# adg731-switches.net
KiCad netlist of a schematic drawn in Altium Designer
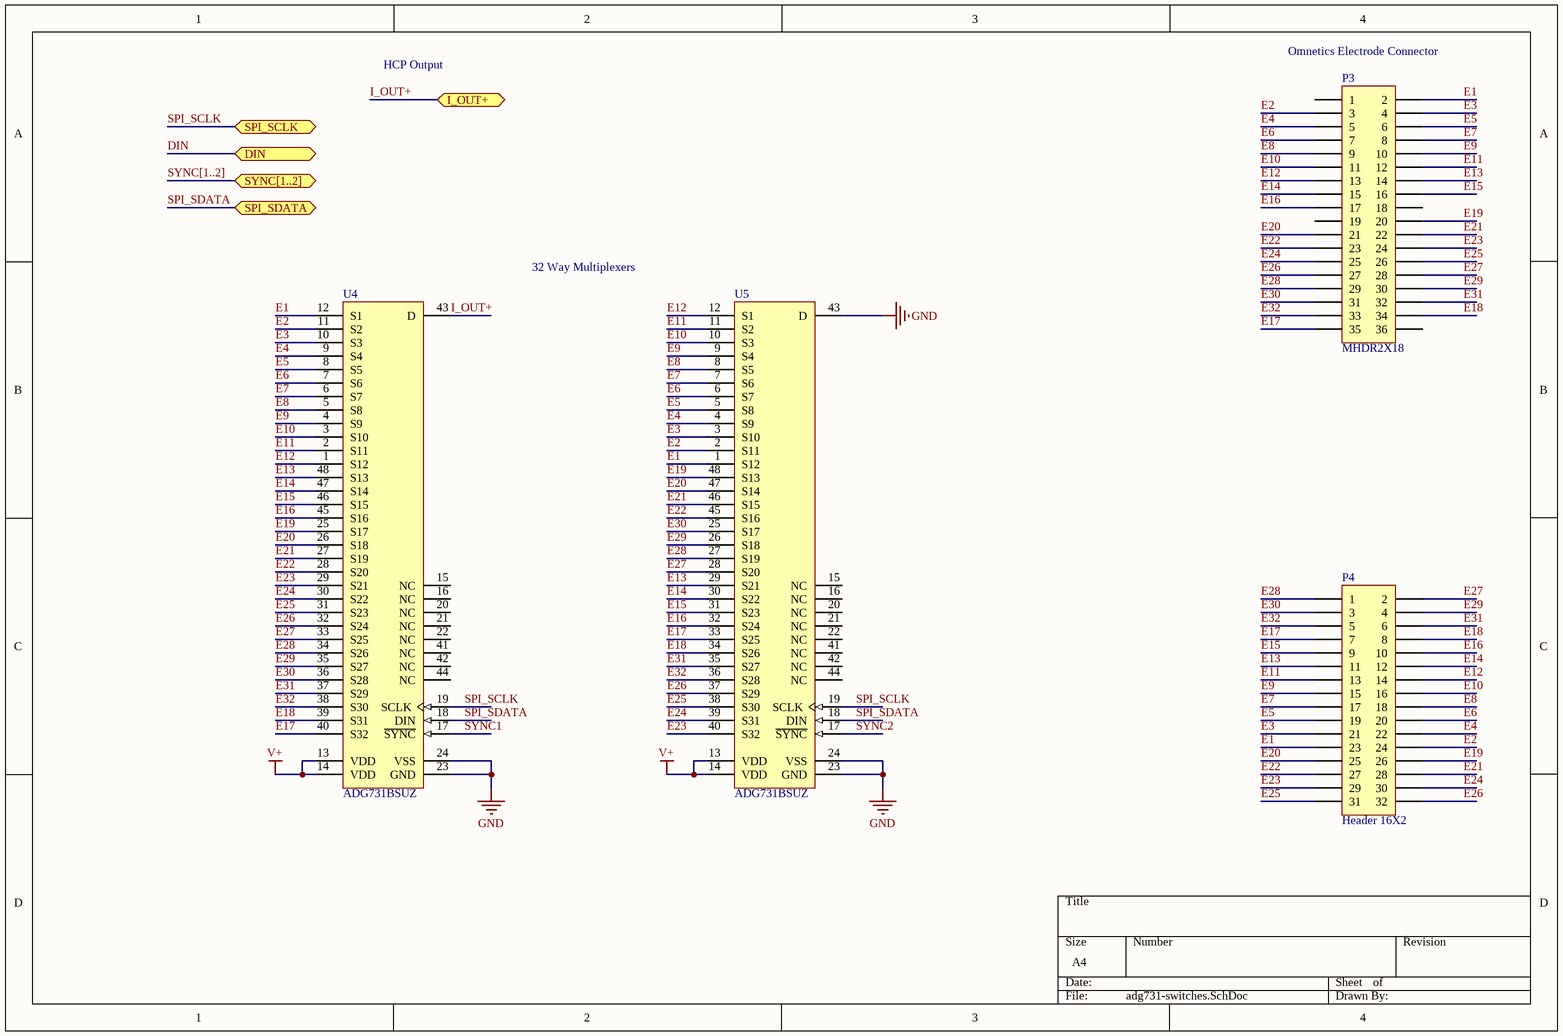
[diagram p0: adg731-switches.SchDoc]

(export (version "E")
  (design (tool "Eeschema 10.0.6"))
  (components
    (comp (ref "P3")
      (value "MHDR2X18")
      (footprint "A79025-001")
      (description "Header, 18-Pin, Dual row")
      (fields (field (name "PUBLISHER") "Altium Limited"))
      (libsource (lib "Miscellaneous Connectors") (part "MHDR2X18"))
    )
    (comp (ref "P4")
      (value "Header 16X2")
      (footprint "FTSH-117-XX-XXX-DH")
      (description "Header, 16-Pin, Dual row")
      (fields (field (name "PUBLISHER") "Altium Limited"))
      (libsource (lib "Miscellaneous Connectors") (part "Header 16X2"))
    )
    (comp (ref "U4")
      (value "ADG731BSUZ")
      (footprint "ADI-SU-48_N")
      (fields (field (name "MANUFACTURER") "Analog Devices"))
      (libsource (lib "Altium Content Vault") (part "CMP-0798-00240-1"))
    )
    (comp (ref "U5")
      (value "ADG731BSUZ")
      (footprint "ADI-SU-48_N")
      (fields (field (name "MANUFACTURER") "Analog Devices"))
      (libsource (lib "Altium Content Vault") (part "CMP-0798-00240-1"))
    )
  )
  (nets
    (net (code "2") (name "/E1") (class "Default")
      (node (ref "P3") (pin "2") (pinfunction "2_2") (pintype "passive"))
      (node (ref "P4") (pin "23") (pinfunction "23_23") (pintype "passive"))
      (node (ref "U4") (pin "12") (pinfunction "S1_12") (pintype "passive"))
      (node (ref "U5") (pin "1") (pinfunction "S12_1") (pintype "passive"))
    )
    (net (code "3") (name "/E2") (class "Default")
      (node (ref "P3") (pin "3") (pinfunction "3_3") (pintype "passive"))
      (node (ref "P4") (pin "24") (pinfunction "24_24") (pintype "passive"))
      (node (ref "U4") (pin "11") (pinfunction "S2_11") (pintype "passive"))
      (node (ref "U5") (pin "2") (pinfunction "S11_2") (pintype "passive"))
    )
    (net (code "4") (name "/E3") (class "Default")
      (node (ref "P3") (pin "4") (pinfunction "4_4") (pintype "passive"))
      (node (ref "P4") (pin "21") (pinfunction "21_21") (pintype "passive"))
      (node (ref "U4") (pin "10") (pinfunction "S3_10") (pintype "passive"))
      (node (ref "U5") (pin "3") (pinfunction "S10_3") (pintype "passive"))
    )
    (net (code "5") (name "/E4") (class "Default")
      (node (ref "P3") (pin "5") (pinfunction "5_5") (pintype "passive"))
      (node (ref "P4") (pin "22") (pinfunction "22_22") (pintype "passive"))
      (node (ref "U4") (pin "9") (pinfunction "S4_9") (pintype "passive"))
      (node (ref "U5") (pin "4") (pinfunction "S9_4") (pintype "passive"))
    )
    (net (code "6") (name "/E5") (class "Default")
      (node (ref "P3") (pin "6") (pinfunction "6_6") (pintype "passive"))
      (node (ref "P4") (pin "19") (pinfunction "19_19") (pintype "passive"))
      (node (ref "U4") (pin "8") (pinfunction "S5_8") (pintype "passive"))
      (node (ref "U5") (pin "5") (pinfunction "S8_5") (pintype "passive"))
    )
    (net (code "7") (name "/E6") (class "Default")
      (node (ref "P3") (pin "7") (pinfunction "7_7") (pintype "passive"))
      (node (ref "P4") (pin "20") (pinfunction "20_20") (pintype "passive"))
      (node (ref "U4") (pin "7") (pinfunction "S6_7") (pintype "passive"))
      (node (ref "U5") (pin "6") (pinfunction "S7_6") (pintype "passive"))
    )
    (net (code "8") (name "/E7") (class "Default")
      (node (ref "P3") (pin "8") (pinfunction "8_8") (pintype "passive"))
      (node (ref "P4") (pin "17") (pinfunction "17_17") (pintype "passive"))
      (node (ref "U4") (pin "6") (pinfunction "S7_6") (pintype "passive"))
      (node (ref "U5") (pin "7") (pinfunction "S6_7") (pintype "passive"))
    )
    (net (code "9") (name "/E8") (class "Default")
      (node (ref "P3") (pin "9") (pinfunction "9_9") (pintype "passive"))
      (node (ref "P4") (pin "18") (pinfunction "18_18") (pintype "passive"))
      (node (ref "U4") (pin "5") (pinfunction "S8_5") (pintype "passive"))
      (node (ref "U5") (pin "8") (pinfunction "S5_8") (pintype "passive"))
    )
    (net (code "10") (name "/E9") (class "Default")
      (node (ref "P3") (pin "10") (pinfunction "10_10") (pintype "passive"))
      (node (ref "P4") (pin "15") (pinfunction "15_15") (pintype "passive"))
      (node (ref "U4") (pin "4") (pinfunction "S9_4") (pintype "passive"))
      (node (ref "U5") (pin "9") (pinfunction "S4_9") (pintype "passive"))
    )
    (net (code "11") (name "/E10") (class "Default")
      (node (ref "P3") (pin "11") (pinfunction "11_11") (pintype "passive"))
      (node (ref "P4") (pin "16") (pinfunction "16_16") (pintype "passive"))
      (node (ref "U4") (pin "3") (pinfunction "S10_3") (pintype "passive"))
      (node (ref "U5") (pin "10") (pinfunction "S3_10") (pintype "passive"))
    )
    (net (code "12") (name "/E11") (class "Default")
      (node (ref "P3") (pin "12") (pinfunction "12_12") (pintype "passive"))
      (node (ref "P4") (pin "13") (pinfunction "13_13") (pintype "passive"))
      (node (ref "U4") (pin "2") (pinfunction "S11_2") (pintype "passive"))
      (node (ref "U5") (pin "11") (pinfunction "S2_11") (pintype "passive"))
    )
    (net (code "13") (name "/E12") (class "Default")
      (node (ref "P3") (pin "13") (pinfunction "13_13") (pintype "passive"))
      (node (ref "P4") (pin "14") (pinfunction "14_14") (pintype "passive"))
      (node (ref "U4") (pin "1") (pinfunction "S12_1") (pintype "passive"))
      (node (ref "U5") (pin "12") (pinfunction "S1_12") (pintype "passive"))
    )
    (net (code "14") (name "/E13") (class "Default")
      (node (ref "P3") (pin "14") (pinfunction "14_14") (pintype "passive"))
      (node (ref "P4") (pin "11") (pinfunction "11_11") (pintype "passive"))
      (node (ref "U4") (pin "48") (pinfunction "S13_48") (pintype "passive"))
      (node (ref "U5") (pin "29") (pinfunction "S21_29") (pintype "passive"))
    )
    (net (code "15") (name "/E14") (class "Default")
      (node (ref "P3") (pin "15") (pinfunction "15_15") (pintype "passive"))
      (node (ref "P4") (pin "12") (pinfunction "12_12") (pintype "passive"))
      (node (ref "U4") (pin "47") (pinfunction "S14_47") (pintype "passive"))
      (node (ref "U5") (pin "30") (pinfunction "S22_30") (pintype "passive"))
    )
    (net (code "16") (name "/E15") (class "Default")
      (node (ref "P3") (pin "16") (pinfunction "16_16") (pintype "passive"))
      (node (ref "P4") (pin "9") (pinfunction "9_9") (pintype "passive"))
      (node (ref "U4") (pin "46") (pinfunction "S15_46") (pintype "passive"))
      (node (ref "U5") (pin "31") (pinfunction "S23_31") (pintype "passive"))
    )
    (net (code "17") (name "/E16") (class "Default")
      (node (ref "P3") (pin "17") (pinfunction "17_17") (pintype "passive"))
      (node (ref "P4") (pin "10") (pinfunction "10_10") (pintype "passive"))
      (node (ref "U4") (pin "45") (pinfunction "S16_45") (pintype "passive"))
      (node (ref "U5") (pin "32") (pinfunction "S24_32") (pintype "passive"))
    )
    (net (code "18") (name "/E17") (class "Default")
      (node (ref "P3") (pin "35") (pinfunction "35_35") (pintype "passive"))
      (node (ref "P4") (pin "7") (pinfunction "7_7") (pintype "passive"))
      (node (ref "U4") (pin "40") (pinfunction "S32_40") (pintype "passive"))
      (node (ref "U5") (pin "33") (pinfunction "S25_33") (pintype "passive"))
    )
    (net (code "19") (name "/E18") (class "Default")
      (node (ref "P3") (pin "34") (pinfunction "34_34") (pintype "passive"))
      (node (ref "P4") (pin "8") (pinfunction "8_8") (pintype "passive"))
      (node (ref "U4") (pin "39") (pinfunction "S31_39") (pintype "passive"))
      (node (ref "U5") (pin "34") (pinfunction "S26_34") (pintype "passive"))
    )
    (net (code "20") (name "/E19") (class "Default")
      (node (ref "P3") (pin "20") (pinfunction "20_20") (pintype "passive"))
      (node (ref "P4") (pin "26") (pinfunction "26_26") (pintype "passive"))
      (node (ref "U4") (pin "25") (pinfunction "S17_25") (pintype "passive"))
      (node (ref "U5") (pin "48") (pinfunction "S13_48") (pintype "passive"))
    )
    (net (code "21") (name "/E20") (class "Default")
      (node (ref "P3") (pin "21") (pinfunction "21_21") (pintype "passive"))
      (node (ref "P4") (pin "25") (pinfunction "25_25") (pintype "passive"))
      (node (ref "U4") (pin "26") (pinfunction "S18_26") (pintype "passive"))
      (node (ref "U5") (pin "47") (pinfunction "S14_47") (pintype "passive"))
    )
    (net (code "22") (name "/E21") (class "Default")
      (node (ref "P3") (pin "22") (pinfunction "22_22") (pintype "passive"))
      (node (ref "P4") (pin "28") (pinfunction "28_28") (pintype "passive"))
      (node (ref "U4") (pin "27") (pinfunction "S19_27") (pintype "passive"))
      (node (ref "U5") (pin "46") (pinfunction "S15_46") (pintype "passive"))
    )
    (net (code "23") (name "/E22") (class "Default")
      (node (ref "P3") (pin "23") (pinfunction "23_23") (pintype "passive"))
      (node (ref "P4") (pin "27") (pinfunction "27_27") (pintype "passive"))
      (node (ref "U4") (pin "28") (pinfunction "S20_28") (pintype "passive"))
      (node (ref "U5") (pin "45") (pinfunction "S16_45") (pintype "passive"))
    )
    (net (code "24") (name "/E23") (class "Default")
      (node (ref "P3") (pin "24") (pinfunction "24_24") (pintype "passive"))
      (node (ref "P4") (pin "29") (pinfunction "29_29") (pintype "passive"))
      (node (ref "U4") (pin "29") (pinfunction "S21_29") (pintype "passive"))
      (node (ref "U5") (pin "40") (pinfunction "S32_40") (pintype "passive"))
    )
    (net (code "25") (name "/E24") (class "Default")
      (node (ref "P3") (pin "25") (pinfunction "25_25") (pintype "passive"))
      (node (ref "P4") (pin "30") (pinfunction "30_30") (pintype "passive"))
      (node (ref "U4") (pin "30") (pinfunction "S22_30") (pintype "passive"))
      (node (ref "U5") (pin "39") (pinfunction "S31_39") (pintype "passive"))
    )
    (net (code "26") (name "/E25") (class "Default")
      (node (ref "P3") (pin "26") (pinfunction "26_26") (pintype "passive"))
      (node (ref "P4") (pin "31") (pinfunction "31_31") (pintype "passive"))
      (node (ref "U4") (pin "31") (pinfunction "S23_31") (pintype "passive"))
      (node (ref "U5") (pin "38") (pinfunction "S30_38") (pintype "passive"))
    )
    (net (code "27") (name "/E26") (class "Default")
      (node (ref "P3") (pin "27") (pinfunction "27_27") (pintype "passive"))
      (node (ref "P4") (pin "32") (pinfunction "32_32") (pintype "passive"))
      (node (ref "U4") (pin "32") (pinfunction "S24_32") (pintype "passive"))
      (node (ref "U5") (pin "37") (pinfunction "S29_37") (pintype "passive"))
    )
    (net (code "28") (name "/E27") (class "Default")
      (node (ref "P3") (pin "28") (pinfunction "28_28") (pintype "passive"))
      (node (ref "P4") (pin "2") (pinfunction "2_2") (pintype "passive"))
      (node (ref "U4") (pin "33") (pinfunction "S25_33") (pintype "passive"))
      (node (ref "U5") (pin "28") (pinfunction "S20_28") (pintype "passive"))
    )
    (net (code "29") (name "/E28") (class "Default")
      (node (ref "P3") (pin "29") (pinfunction "29_29") (pintype "passive"))
      (node (ref "P4") (pin "1") (pinfunction "1_1") (pintype "passive"))
      (node (ref "U4") (pin "34") (pinfunction "S26_34") (pintype "passive"))
      (node (ref "U5") (pin "27") (pinfunction "S19_27") (pintype "passive"))
    )
    (net (code "30") (name "/E29") (class "Default")
      (node (ref "P3") (pin "30") (pinfunction "30_30") (pintype "passive"))
      (node (ref "P4") (pin "4") (pinfunction "4_4") (pintype "passive"))
      (node (ref "U4") (pin "35") (pinfunction "S27_35") (pintype "passive"))
      (node (ref "U5") (pin "26") (pinfunction "S18_26") (pintype "passive"))
    )
    (net (code "31") (name "/E30") (class "Default")
      (node (ref "P3") (pin "31") (pinfunction "31_31") (pintype "passive"))
      (node (ref "P4") (pin "3") (pinfunction "3_3") (pintype "passive"))
      (node (ref "U4") (pin "36") (pinfunction "S28_36") (pintype "passive"))
      (node (ref "U5") (pin "25") (pinfunction "S17_25") (pintype "passive"))
    )
    (net (code "32") (name "/E31") (class "Default")
      (node (ref "P3") (pin "32") (pinfunction "32_32") (pintype "passive"))
      (node (ref "P4") (pin "6") (pinfunction "6_6") (pintype "passive"))
      (node (ref "U4") (pin "37") (pinfunction "S29_37") (pintype "passive"))
      (node (ref "U5") (pin "35") (pinfunction "S27_35") (pintype "passive"))
    )
    (net (code "33") (name "/E32") (class "Default")
      (node (ref "P3") (pin "33") (pinfunction "33_33") (pintype "passive"))
      (node (ref "P4") (pin "5") (pinfunction "5_5") (pintype "passive"))
      (node (ref "U4") (pin "38") (pinfunction "S30_38") (pintype "passive"))
      (node (ref "U5") (pin "36") (pinfunction "S28_36") (pintype "passive"))
    )
    (net (code "34") (name "/I_OUT+") (class "Default")
      (node (ref "U4") (pin "43") (pinfunction "D_43") (pintype "passive"))
    )
    (net (code "35") (name "/SPI_SCLK") (class "Default")
      (node (ref "U4") (pin "19") (pinfunction "SCLK_19") (pintype "input"))
      (node (ref "U5") (pin "19") (pinfunction "SCLK_19") (pintype "input"))
    )
    (net (code "36") (name "/SPI_SDATA") (class "Default")
      (node (ref "U4") (pin "18") (pinfunction "DIN_18") (pintype "input"))
      (node (ref "U5") (pin "18") (pinfunction "DIN_18") (pintype "input"))
    )
    (net (code "37") (name "/SYNC1") (class "Default")
      (node (ref "U4") (pin "17") (pinfunction "~{SYNC}_17") (pintype "input"))
    )
    (net (code "38") (name "/SYNC2") (class "Default")
      (node (ref "U5") (pin "17") (pinfunction "~{SYNC}_17") (pintype "input"))
    )
    (net (code "40") (name "GND") (class "Default")
      (node (ref "U4") (pin "23") (pinfunction "GND_23") (pintype "power_in"))
      (node (ref "U4") (pin "24") (pinfunction "VSS_24") (pintype "power_in"))
      (node (ref "U5") (pin "23") (pinfunction "GND_23") (pintype "power_in"))
      (node (ref "U5") (pin "24") (pinfunction "VSS_24") (pintype "power_in"))
      (node (ref "U5") (pin "43") (pinfunction "D_43") (pintype "passive"))
    )
    (net (code "41") (name "V+") (class "Default")
      (node (ref "U4") (pin "13") (pinfunction "VDD_13") (pintype "power_in"))
      (node (ref "U4") (pin "14") (pinfunction "VDD_14") (pintype "power_in"))
      (node (ref "U5") (pin "13") (pinfunction "VDD_13") (pintype "power_in"))
      (node (ref "U5") (pin "14") (pinfunction "VDD_14") (pintype "power_in"))
    )
    (net (code "42") (name "unconnected-(P3-Pad1)") (class "Default")
      (node (ref "P3") (pin "1") (pinfunction "1_1") (pintype "passive"))
    )
    (net (code "43") (name "unconnected-(P3-Pad18)") (class "Default")
      (node (ref "P3") (pin "18") (pinfunction "18_18") (pintype "passive"))
    )
    (net (code "44") (name "unconnected-(P3-Pad19)") (class "Default")
      (node (ref "P3") (pin "19") (pinfunction "19_19") (pintype "passive"))
    )
    (net (code "45") (name "unconnected-(P3-Pad36)") (class "Default")
      (node (ref "P3") (pin "36") (pinfunction "36_36") (pintype "passive"))
    )
    (net (code "46") (name "unconnected-(U4-NC-Pad15)") (class "Default")
      (node (ref "U4") (pin "15") (pinfunction "NC_15") (pintype "passive"))
    )
    (net (code "47") (name "unconnected-(U4-NC-Pad16)") (class "Default")
      (node (ref "U4") (pin "16") (pinfunction "NC_16") (pintype "passive"))
    )
    (net (code "48") (name "unconnected-(U4-NC-Pad20)") (class "Default")
      (node (ref "U4") (pin "20") (pinfunction "NC_20") (pintype "passive"))
    )
    (net (code "49") (name "unconnected-(U4-NC-Pad21)") (class "Default")
      (node (ref "U4") (pin "21") (pinfunction "NC_21") (pintype "passive"))
    )
    (net (code "50") (name "unconnected-(U4-NC-Pad22)") (class "Default")
      (node (ref "U4") (pin "22") (pinfunction "NC_22") (pintype "passive"))
    )
    (net (code "51") (name "unconnected-(U4-NC-Pad41)") (class "Default")
      (node (ref "U4") (pin "41") (pinfunction "NC_41") (pintype "passive"))
    )
    (net (code "52") (name "unconnected-(U4-NC-Pad42)") (class "Default")
      (node (ref "U4") (pin "42") (pinfunction "NC_42") (pintype "passive"))
    )
    (net (code "53") (name "unconnected-(U4-NC-Pad44)") (class "Default")
      (node (ref "U4") (pin "44") (pinfunction "NC_44") (pintype "passive"))
    )
    (net (code "54") (name "unconnected-(U5-NC-Pad15)") (class "Default")
      (node (ref "U5") (pin "15") (pinfunction "NC_15") (pintype "passive"))
    )
    (net (code "55") (name "unconnected-(U5-NC-Pad16)") (class "Default")
      (node (ref "U5") (pin "16") (pinfunction "NC_16") (pintype "passive"))
    )
    (net (code "56") (name "unconnected-(U5-NC-Pad20)") (class "Default")
      (node (ref "U5") (pin "20") (pinfunction "NC_20") (pintype "passive"))
    )
    (net (code "57") (name "unconnected-(U5-NC-Pad21)") (class "Default")
      (node (ref "U5") (pin "21") (pinfunction "NC_21") (pintype "passive"))
    )
    (net (code "58") (name "unconnected-(U5-NC-Pad22)") (class "Default")
      (node (ref "U5") (pin "22") (pinfunction "NC_22") (pintype "passive"))
    )
    (net (code "59") (name "unconnected-(U5-NC-Pad41)") (class "Default")
      (node (ref "U5") (pin "41") (pinfunction "NC_41") (pintype "passive"))
    )
    (net (code "60") (name "unconnected-(U5-NC-Pad42)") (class "Default")
      (node (ref "U5") (pin "42") (pinfunction "NC_42") (pintype "passive"))
    )
    (net (code "61") (name "unconnected-(U5-NC-Pad44)") (class "Default")
      (node (ref "U5") (pin "44") (pinfunction "NC_44") (pintype "passive"))
    )
  )
)
